# kalibracija.net
KiCad netlist of a schematic drawn in Altium Designer
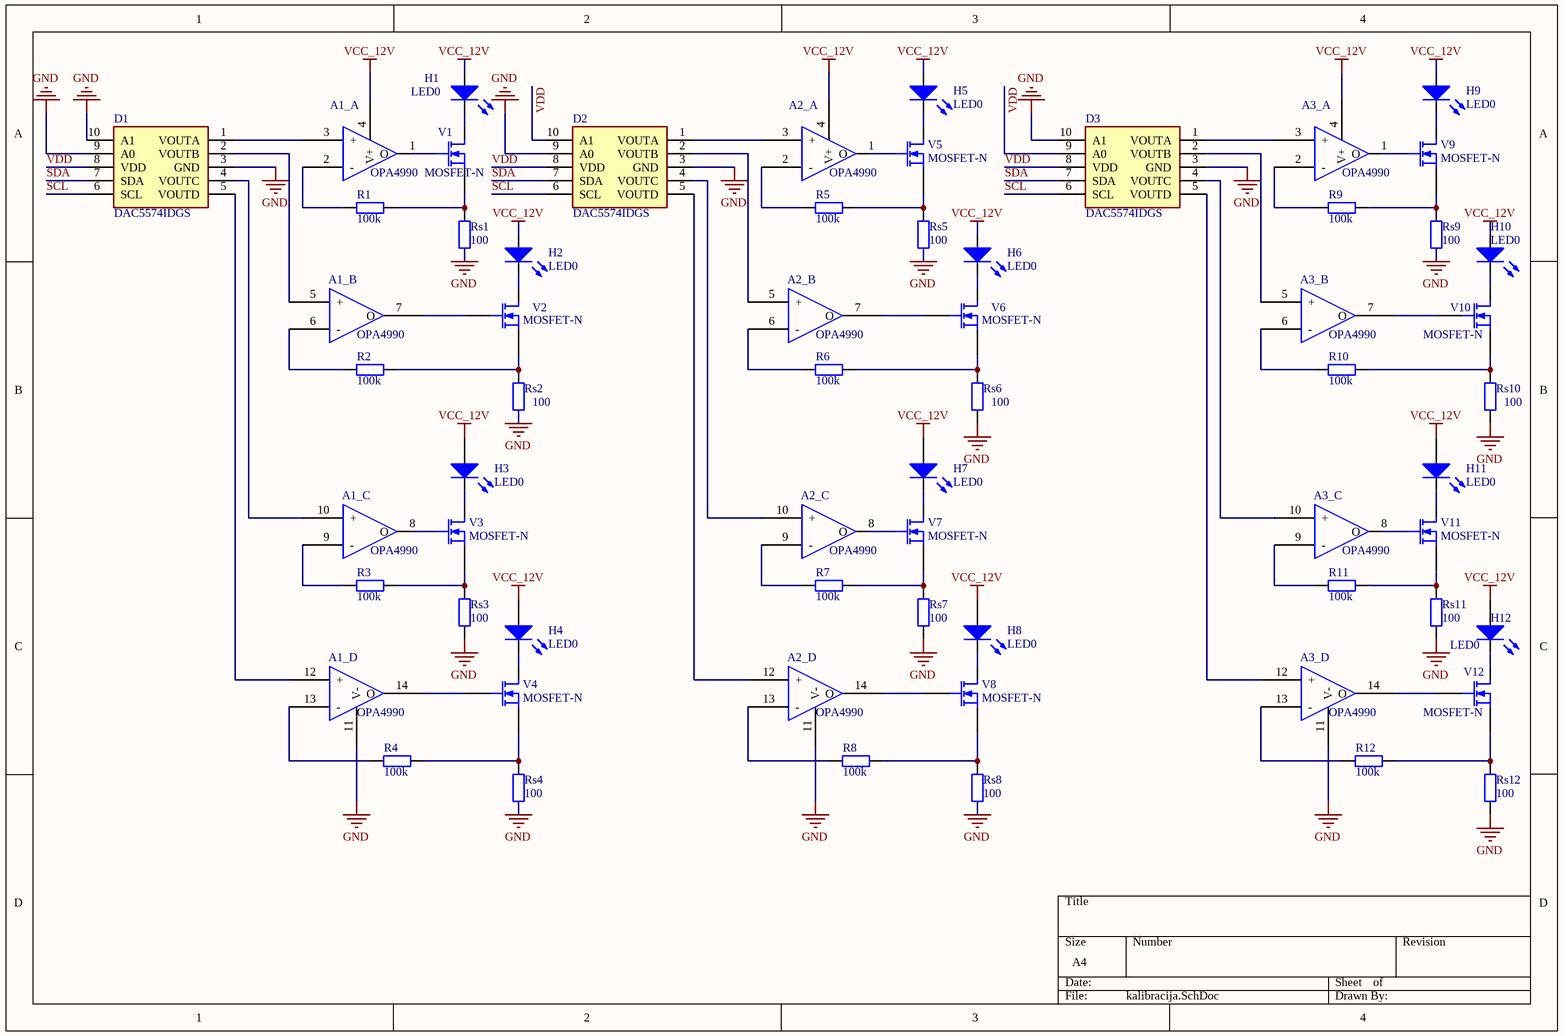
[diagram p0: kalibracija.SchDoc]

(export (version "E")
  (design (tool "Eeschema 10.0.6"))
  (components
    (comp (ref "A1_")
      (value "OPA4990")
      (footprint "SOIC127P600X175-14N")
      (libsource (lib "Kalibracija") (part "OPA4990"))
    )
    (comp (ref "A2_")
      (value "OPA4990")
      (footprint "SOIC127P600X175-14N")
      (libsource (lib "Kalibracija") (part "OPA4990"))
    )
    (comp (ref "A3_")
      (value "OPA4990")
      (footprint "SOIC127P600X175-14N")
      (libsource (lib "Kalibracija") (part "OPA4990"))
    )
    (comp (ref "D1")
      (value "DAC5574IDGS")
      (footprint "SamacSys:SOP50P490X110-10N")
      (description "Integrated Circuit")
      (fields
        (field (name "MOUSER PART NUMBER") "595-DAC5574IDGS")
        (field (name "RS PART NUMBER") "6621533P")
      )
      (libsource (lib "*") (part "DAC5574IDGS"))
    )
    (comp (ref "D2")
      (value "DAC5574IDGS")
      (footprint "SamacSys:SOP50P490X110-10N")
      (description "Integrated Circuit")
      (fields
        (field (name "MOUSER PART NUMBER") "595-DAC5574IDGS")
        (field (name "RS PART NUMBER") "6621533P")
      )
      (libsource (lib "*") (part "DAC5574IDGS"))
    )
    (comp (ref "D3")
      (value "DAC5574IDGS")
      (footprint "SamacSys:SOP50P490X110-10N")
      (description "Integrated Circuit")
      (fields
        (field (name "MOUSER PART NUMBER") "595-DAC5574IDGS")
        (field (name "RS PART NUMBER") "6621533P")
      )
      (libsource (lib "*") (part "DAC5574IDGS"))
    )
    (comp (ref "H1")
      (value "LED0")
      (footprint "HDR1X2")
      (description "Typical INFRARED GaAs LED")
      (fields (field (name "PUBLISHER") "Altium Limited"))
      (libsource (lib "Miscellaneous Devices") (part "LED0"))
    )
    (comp (ref "H2")
      (value "LED0")
      (footprint "HDR1X2")
      (description "Typical INFRARED GaAs LED")
      (fields (field (name "PUBLISHER") "Altium Limited"))
      (libsource (lib "Miscellaneous Devices") (part "LED0"))
    )
    (comp (ref "H3")
      (value "LED0")
      (footprint "HDR1X2")
      (description "Typical INFRARED GaAs LED")
      (fields (field (name "PUBLISHER") "Altium Limited"))
      (libsource (lib "Miscellaneous Devices") (part "LED0"))
    )
    (comp (ref "H4")
      (value "LED0")
      (footprint "HDR1X2")
      (description "Typical INFRARED GaAs LED")
      (fields (field (name "PUBLISHER") "Altium Limited"))
      (libsource (lib "Miscellaneous Devices") (part "LED0"))
    )
    (comp (ref "H5")
      (value "LED0")
      (footprint "HDR1X2")
      (description "Typical INFRARED GaAs LED")
      (fields (field (name "PUBLISHER") "Altium Limited"))
      (libsource (lib "Miscellaneous Devices") (part "LED0"))
    )
    (comp (ref "H6")
      (value "LED0")
      (footprint "HDR1X2")
      (description "Typical INFRARED GaAs LED")
      (fields (field (name "PUBLISHER") "Altium Limited"))
      (libsource (lib "Miscellaneous Devices") (part "LED0"))
    )
    (comp (ref "H7")
      (value "LED0")
      (footprint "HDR1X2")
      (description "Typical INFRARED GaAs LED")
      (fields (field (name "PUBLISHER") "Altium Limited"))
      (libsource (lib "Miscellaneous Devices") (part "LED0"))
    )
    (comp (ref "H8")
      (value "LED0")
      (footprint "HDR1X2")
      (description "Typical INFRARED GaAs LED")
      (fields (field (name "PUBLISHER") "Altium Limited"))
      (libsource (lib "Miscellaneous Devices") (part "LED0"))
    )
    (comp (ref "H9")
      (value "LED0")
      (footprint "HDR1X2")
      (description "Typical INFRARED GaAs LED")
      (fields (field (name "PUBLISHER") "Altium Limited"))
      (libsource (lib "Miscellaneous Devices") (part "LED0"))
    )
    (comp (ref "H10")
      (value "LED0")
      (footprint "HDR1X2")
      (description "Typical INFRARED GaAs LED")
      (fields (field (name "PUBLISHER") "Altium Limited"))
      (libsource (lib "Miscellaneous Devices") (part "LED0"))
    )
    (comp (ref "H11")
      (value "LED0")
      (footprint "HDR1X2")
      (description "Typical INFRARED GaAs LED")
      (fields (field (name "PUBLISHER") "Altium Limited"))
      (libsource (lib "Miscellaneous Devices") (part "LED0"))
    )
    (comp (ref "H12")
      (value "LED0")
      (footprint "HDR1X2")
      (description "Typical INFRARED GaAs LED")
      (fields (field (name "PUBLISHER") "Altium Limited"))
      (libsource (lib "Miscellaneous Devices") (part "LED0"))
    )
    (comp (ref "R1")
      (value "100k")
      (footprint "AXIAL-0.4")
      (description "Resistor")
      (fields (field (name "PUBLISHER") "Altium Limited"))
      (libsource (lib "") (part "Res2_1"))
    )
    (comp (ref "R2")
      (value "100k")
      (footprint "AXIAL-0.4")
      (description "Resistor")
      (fields (field (name "PUBLISHER") "Altium Limited"))
      (libsource (lib "") (part "Res2_1"))
    )
    (comp (ref "R3")
      (value "100k")
      (footprint "AXIAL-0.4")
      (description "Resistor")
      (fields (field (name "PUBLISHER") "Altium Limited"))
      (libsource (lib "") (part "Res2_1"))
    )
    (comp (ref "R4")
      (value "100k")
      (footprint "AXIAL-0.4")
      (description "Resistor")
      (fields (field (name "PUBLISHER") "Altium Limited"))
      (libsource (lib "") (part "Res2_1"))
    )
    (comp (ref "R5")
      (value "100k")
      (footprint "AXIAL-0.4")
      (description "Resistor")
      (fields (field (name "PUBLISHER") "Altium Limited"))
      (libsource (lib "") (part "Res2_1"))
    )
    (comp (ref "R6")
      (value "100k")
      (footprint "AXIAL-0.4")
      (description "Resistor")
      (fields (field (name "PUBLISHER") "Altium Limited"))
      (libsource (lib "") (part "Res2_1"))
    )
    (comp (ref "R7")
      (value "100k")
      (footprint "AXIAL-0.4")
      (description "Resistor")
      (fields (field (name "PUBLISHER") "Altium Limited"))
      (libsource (lib "") (part "Res2_1"))
    )
    (comp (ref "R8")
      (value "100k")
      (footprint "AXIAL-0.4")
      (description "Resistor")
      (fields (field (name "PUBLISHER") "Altium Limited"))
      (libsource (lib "") (part "Res2_1"))
    )
    (comp (ref "R9")
      (value "100k")
      (footprint "AXIAL-0.4")
      (description "Resistor")
      (fields (field (name "PUBLISHER") "Altium Limited"))
      (libsource (lib "") (part "Res2_1"))
    )
    (comp (ref "R10")
      (value "100k")
      (footprint "AXIAL-0.4")
      (description "Resistor")
      (fields (field (name "PUBLISHER") "Altium Limited"))
      (libsource (lib "") (part "Res2_1"))
    )
    (comp (ref "R11")
      (value "100k")
      (footprint "AXIAL-0.4")
      (description "Resistor")
      (fields (field (name "PUBLISHER") "Altium Limited"))
      (libsource (lib "") (part "Res2_1"))
    )
    (comp (ref "R12")
      (value "100k")
      (footprint "AXIAL-0.4")
      (description "Resistor")
      (fields (field (name "PUBLISHER") "Altium Limited"))
      (libsource (lib "") (part "Res2_1"))
    )
    (comp (ref "Rs1")
      (value "100")
      (footprint "AXIAL-0.4")
      (description "Resistor")
      (fields (field (name "PUBLISHER") "Altium Limited"))
      (libsource (lib "Miscellaneous Devices") (part "Res2"))
    )
    (comp (ref "Rs2")
      (value "100")
      (footprint "AXIAL-0.4")
      (description "Resistor")
      (fields (field (name "PUBLISHER") "Altium Limited"))
      (libsource (lib "Miscellaneous Devices") (part "Res2"))
    )
    (comp (ref "Rs3")
      (value "100")
      (footprint "AXIAL-0.4")
      (description "Resistor")
      (fields (field (name "PUBLISHER") "Altium Limited"))
      (libsource (lib "Miscellaneous Devices") (part "Res2"))
    )
    (comp (ref "Rs4")
      (value "100")
      (footprint "AXIAL-0.4")
      (description "Resistor")
      (fields (field (name "PUBLISHER") "Altium Limited"))
      (libsource (lib "Miscellaneous Devices") (part "Res2"))
    )
    (comp (ref "Rs5")
      (value "100")
      (footprint "AXIAL-0.4")
      (description "Resistor")
      (fields (field (name "PUBLISHER") "Altium Limited"))
      (libsource (lib "Miscellaneous Devices") (part "Res2"))
    )
    (comp (ref "Rs6")
      (value "100")
      (footprint "AXIAL-0.4")
      (description "Resistor")
      (fields (field (name "PUBLISHER") "Altium Limited"))
      (libsource (lib "Miscellaneous Devices") (part "Res2"))
    )
    (comp (ref "Rs7")
      (value "100")
      (footprint "AXIAL-0.4")
      (description "Resistor")
      (fields (field (name "PUBLISHER") "Altium Limited"))
      (libsource (lib "Miscellaneous Devices") (part "Res2"))
    )
    (comp (ref "Rs8")
      (value "100")
      (footprint "AXIAL-0.4")
      (description "Resistor")
      (fields (field (name "PUBLISHER") "Altium Limited"))
      (libsource (lib "Miscellaneous Devices") (part "Res2"))
    )
    (comp (ref "Rs9")
      (value "100")
      (footprint "AXIAL-0.4")
      (description "Resistor")
      (fields (field (name "PUBLISHER") "Altium Limited"))
      (libsource (lib "Miscellaneous Devices") (part "Res2"))
    )
    (comp (ref "Rs10")
      (value "100")
      (footprint "AXIAL-0.4")
      (description "Resistor")
      (fields (field (name "PUBLISHER") "Altium Limited"))
      (libsource (lib "Miscellaneous Devices") (part "Res2"))
    )
    (comp (ref "Rs11")
      (value "100")
      (footprint "AXIAL-0.4")
      (description "Resistor")
      (fields (field (name "PUBLISHER") "Altium Limited"))
      (libsource (lib "Miscellaneous Devices") (part "Res2"))
    )
    (comp (ref "Rs12")
      (value "100")
      (footprint "AXIAL-0.4")
      (description "Resistor")
      (fields (field (name "PUBLISHER") "Altium Limited"))
      (libsource (lib "Miscellaneous Devices") (part "Res2"))
    )
    (comp (ref "V1")
      (value "MOSFET-N")
      (footprint "TO-92")
      (description "N-Channel MOSFET")
      (fields (field (name "PUBLISHER") "Altium Limited"))
      (libsource (lib "Miscellaneous Devices") (part "MOSFET-N"))
    )
    (comp (ref "V2")
      (value "MOSFET-N")
      (footprint "TO-92")
      (description "N-Channel MOSFET")
      (fields (field (name "PUBLISHER") "Altium Limited"))
      (libsource (lib "Miscellaneous Devices") (part "MOSFET-N"))
    )
    (comp (ref "V3")
      (value "MOSFET-N")
      (footprint "TO-92")
      (description "N-Channel MOSFET")
      (fields (field (name "PUBLISHER") "Altium Limited"))
      (libsource (lib "Miscellaneous Devices") (part "MOSFET-N"))
    )
    (comp (ref "V4")
      (value "MOSFET-N")
      (footprint "TO-92")
      (description "N-Channel MOSFET")
      (fields (field (name "PUBLISHER") "Altium Limited"))
      (libsource (lib "Miscellaneous Devices") (part "MOSFET-N"))
    )
    (comp (ref "V5")
      (value "MOSFET-N")
      (footprint "TO-92")
      (description "N-Channel MOSFET")
      (fields (field (name "PUBLISHER") "Altium Limited"))
      (libsource (lib "Miscellaneous Devices") (part "MOSFET-N"))
    )
    (comp (ref "V6")
      (value "MOSFET-N")
      (footprint "TO-92")
      (description "N-Channel MOSFET")
      (fields (field (name "PUBLISHER") "Altium Limited"))
      (libsource (lib "Miscellaneous Devices") (part "MOSFET-N"))
    )
    (comp (ref "V7")
      (value "MOSFET-N")
      (footprint "TO-92")
      (description "N-Channel MOSFET")
      (fields (field (name "PUBLISHER") "Altium Limited"))
      (libsource (lib "Miscellaneous Devices") (part "MOSFET-N"))
    )
    (comp (ref "V8")
      (value "MOSFET-N")
      (footprint "TO-92")
      (description "N-Channel MOSFET")
      (fields (field (name "PUBLISHER") "Altium Limited"))
      (libsource (lib "Miscellaneous Devices") (part "MOSFET-N"))
    )
    (comp (ref "V9")
      (value "MOSFET-N")
      (footprint "TO-92")
      (description "N-Channel MOSFET")
      (fields (field (name "PUBLISHER") "Altium Limited"))
      (libsource (lib "Miscellaneous Devices") (part "MOSFET-N"))
    )
    (comp (ref "V10")
      (value "MOSFET-N")
      (footprint "TO-92")
      (description "N-Channel MOSFET")
      (fields (field (name "PUBLISHER") "Altium Limited"))
      (libsource (lib "Miscellaneous Devices") (part "MOSFET-N"))
    )
    (comp (ref "V11")
      (value "MOSFET-N")
      (footprint "TO-92")
      (description "N-Channel MOSFET")
      (fields (field (name "PUBLISHER") "Altium Limited"))
      (libsource (lib "Miscellaneous Devices") (part "MOSFET-N"))
    )
    (comp (ref "V12")
      (value "MOSFET-N")
      (footprint "TO-92")
      (description "N-Channel MOSFET")
      (fields (field (name "PUBLISHER") "Altium Limited"))
      (libsource (lib "Miscellaneous Devices") (part "MOSFET-N"))
    )
  )
  (nets
    (net (code "1") (name "/SCL") (class "Default")
      (node (ref "D1") (pin "6") (pinfunction "SCL_6") (pintype "passive"))
      (node (ref "D2") (pin "6") (pinfunction "SCL_6") (pintype "passive"))
      (node (ref "D3") (pin "6") (pinfunction "SCL_6") (pintype "passive"))
    )
    (net (code "2") (name "/SDA") (class "Default")
      (node (ref "D1") (pin "7") (pinfunction "SDA_7") (pintype "passive"))
      (node (ref "D2") (pin "7") (pinfunction "SDA_7") (pintype "passive"))
      (node (ref "D3") (pin "7") (pinfunction "SDA_7") (pintype "passive"))
    )
    (net (code "3") (name "/VDD") (class "Default")
      (node (ref "D1") (pin "8") (pinfunction "VDD_8") (pintype "passive"))
      (node (ref "D2") (pin "10") (pinfunction "A1_10") (pintype "passive"))
      (node (ref "D2") (pin "8") (pinfunction "VDD_8") (pintype "passive"))
      (node (ref "D3") (pin "8") (pinfunction "VDD_8") (pintype "passive"))
      (node (ref "D3") (pin "9") (pinfunction "A0_9") (pintype "passive"))
    )
    (net (code "4") (name "GND") (class "Default")
      (node (ref "A1_") (pin "11") (pinfunction "V-_11") (pintype "power_in"))
      (node (ref "A2_") (pin "11") (pinfunction "V-_11") (pintype "power_in"))
      (node (ref "A3_") (pin "11") (pinfunction "V-_11") (pintype "power_in"))
      (node (ref "D1") (pin "10") (pinfunction "A1_10") (pintype "passive"))
      (node (ref "D1") (pin "3") (pinfunction "GND_3") (pintype "passive"))
      (node (ref "D1") (pin "9") (pinfunction "A0_9") (pintype "passive"))
      (node (ref "D2") (pin "3") (pinfunction "GND_3") (pintype "passive"))
      (node (ref "D2") (pin "9") (pinfunction "A0_9") (pintype "passive"))
      (node (ref "D3") (pin "10") (pinfunction "A1_10") (pintype "passive"))
      (node (ref "D3") (pin "3") (pinfunction "GND_3") (pintype "passive"))
      (node (ref "Rs1") (pin "1") (pinfunction "1_1") (pintype "passive"))
      (node (ref "Rs10") (pin "1") (pinfunction "1_1") (pintype "passive"))
      (node (ref "Rs11") (pin "1") (pinfunction "1_1") (pintype "passive"))
      (node (ref "Rs12") (pin "1") (pinfunction "1_1") (pintype "passive"))
      (node (ref "Rs2") (pin "1") (pinfunction "1_1") (pintype "passive"))
      (node (ref "Rs3") (pin "1") (pinfunction "1_1") (pintype "passive"))
      (node (ref "Rs4") (pin "1") (pinfunction "1_1") (pintype "passive"))
      (node (ref "Rs5") (pin "1") (pinfunction "1_1") (pintype "passive"))
      (node (ref "Rs6") (pin "1") (pinfunction "1_1") (pintype "passive"))
      (node (ref "Rs7") (pin "1") (pinfunction "1_1") (pintype "passive"))
      (node (ref "Rs8") (pin "1") (pinfunction "1_1") (pintype "passive"))
      (node (ref "Rs9") (pin "1") (pinfunction "1_1") (pintype "passive"))
    )
    (net (code "5") (name "Net-(A1_A-+)") (class "Default")
      (node (ref "A1_") (pin "3") (pinfunction "+_3") (pintype "passive"))
      (node (ref "D1") (pin "1") (pinfunction "VOUTA_1") (pintype "passive"))
    )
    (net (code "6") (name "Net-(A1_A--)") (class "Default")
      (node (ref "A1_") (pin "2") (pinfunction "-_2") (pintype "passive"))
      (node (ref "R1") (pin "1") (pinfunction "1_1") (pintype "passive"))
    )
    (net (code "7") (name "Net-(A1_A-O)") (class "Default")
      (node (ref "A1_") (pin "1") (pinfunction "O_1") (pintype "passive"))
      (node (ref "V1") (pin "2") (pinfunction "G_2") (pintype "passive"))
    )
    (net (code "8") (name "Net-(A1_B-+)") (class "Default")
      (node (ref "A1_") (pin "5") (pinfunction "+_5") (pintype "passive"))
      (node (ref "D1") (pin "2") (pinfunction "VOUTB_2") (pintype "passive"))
    )
    (net (code "9") (name "Net-(A1_B--)") (class "Default")
      (node (ref "A1_") (pin "6") (pinfunction "-_6") (pintype "passive"))
      (node (ref "R2") (pin "1") (pinfunction "1_1") (pintype "passive"))
    )
    (net (code "10") (name "Net-(A1_B-O)") (class "Default")
      (node (ref "A1_") (pin "7") (pinfunction "O_7") (pintype "passive"))
      (node (ref "V2") (pin "2") (pinfunction "G_2") (pintype "passive"))
    )
    (net (code "11") (name "Net-(A1_C-+)") (class "Default")
      (node (ref "A1_") (pin "10") (pinfunction "+_10") (pintype "passive"))
      (node (ref "D1") (pin "4") (pinfunction "VOUTC_4") (pintype "passive"))
    )
    (net (code "12") (name "Net-(A1_C--)") (class "Default")
      (node (ref "A1_") (pin "9") (pinfunction "-_9") (pintype "passive"))
      (node (ref "R3") (pin "1") (pinfunction "1_1") (pintype "passive"))
    )
    (net (code "13") (name "Net-(A1_C-O)") (class "Default")
      (node (ref "A1_") (pin "8") (pinfunction "O_8") (pintype "passive"))
      (node (ref "V3") (pin "2") (pinfunction "G_2") (pintype "passive"))
    )
    (net (code "14") (name "Net-(A1_D-+)") (class "Default")
      (node (ref "A1_") (pin "12") (pinfunction "+_12") (pintype "passive"))
      (node (ref "D1") (pin "5") (pinfunction "VOUTD_5") (pintype "passive"))
    )
    (net (code "15") (name "Net-(A1_D--)") (class "Default")
      (node (ref "A1_") (pin "13") (pinfunction "-_13") (pintype "passive"))
      (node (ref "R4") (pin "1") (pinfunction "1_1") (pintype "passive"))
    )
    (net (code "16") (name "Net-(A1_D-O)") (class "Default")
      (node (ref "A1_") (pin "14") (pinfunction "O_14") (pintype "passive"))
      (node (ref "V4") (pin "2") (pinfunction "G_2") (pintype "passive"))
    )
    (net (code "17") (name "Net-(A2_A-+)") (class "Default")
      (node (ref "A2_") (pin "3") (pinfunction "+_3") (pintype "passive"))
      (node (ref "D2") (pin "1") (pinfunction "VOUTA_1") (pintype "passive"))
    )
    (net (code "18") (name "Net-(A2_A--)") (class "Default")
      (node (ref "A2_") (pin "2") (pinfunction "-_2") (pintype "passive"))
      (node (ref "R5") (pin "1") (pinfunction "1_1") (pintype "passive"))
    )
    (net (code "19") (name "Net-(A2_A-O)") (class "Default")
      (node (ref "A2_") (pin "1") (pinfunction "O_1") (pintype "passive"))
      (node (ref "V5") (pin "2") (pinfunction "G_2") (pintype "passive"))
    )
    (net (code "20") (name "Net-(A2_B-+)") (class "Default")
      (node (ref "A2_") (pin "5") (pinfunction "+_5") (pintype "passive"))
      (node (ref "D2") (pin "2") (pinfunction "VOUTB_2") (pintype "passive"))
    )
    (net (code "21") (name "Net-(A2_B--)") (class "Default")
      (node (ref "A2_") (pin "6") (pinfunction "-_6") (pintype "passive"))
      (node (ref "R6") (pin "1") (pinfunction "1_1") (pintype "passive"))
    )
    (net (code "22") (name "Net-(A2_B-O)") (class "Default")
      (node (ref "A2_") (pin "7") (pinfunction "O_7") (pintype "passive"))
      (node (ref "V6") (pin "2") (pinfunction "G_2") (pintype "passive"))
    )
    (net (code "23") (name "Net-(A2_C-+)") (class "Default")
      (node (ref "A2_") (pin "10") (pinfunction "+_10") (pintype "passive"))
      (node (ref "D2") (pin "4") (pinfunction "VOUTC_4") (pintype "passive"))
    )
    (net (code "24") (name "Net-(A2_C--)") (class "Default")
      (node (ref "A2_") (pin "9") (pinfunction "-_9") (pintype "passive"))
      (node (ref "R7") (pin "1") (pinfunction "1_1") (pintype "passive"))
    )
    (net (code "25") (name "Net-(A2_C-O)") (class "Default")
      (node (ref "A2_") (pin "8") (pinfunction "O_8") (pintype "passive"))
      (node (ref "V7") (pin "2") (pinfunction "G_2") (pintype "passive"))
    )
    (net (code "26") (name "Net-(A2_D-+)") (class "Default")
      (node (ref "A2_") (pin "12") (pinfunction "+_12") (pintype "passive"))
      (node (ref "D2") (pin "5") (pinfunction "VOUTD_5") (pintype "passive"))
    )
    (net (code "27") (name "Net-(A2_D--)") (class "Default")
      (node (ref "A2_") (pin "13") (pinfunction "-_13") (pintype "passive"))
      (node (ref "R8") (pin "1") (pinfunction "1_1") (pintype "passive"))
    )
    (net (code "28") (name "Net-(A2_D-O)") (class "Default")
      (node (ref "A2_") (pin "14") (pinfunction "O_14") (pintype "passive"))
      (node (ref "V8") (pin "2") (pinfunction "G_2") (pintype "passive"))
    )
    (net (code "29") (name "Net-(A3_A-+)") (class "Default")
      (node (ref "A3_") (pin "3") (pinfunction "+_3") (pintype "passive"))
      (node (ref "D3") (pin "1") (pinfunction "VOUTA_1") (pintype "passive"))
    )
    (net (code "30") (name "Net-(A3_A--)") (class "Default")
      (node (ref "A3_") (pin "2") (pinfunction "-_2") (pintype "passive"))
      (node (ref "R9") (pin "1") (pinfunction "1_1") (pintype "passive"))
    )
    (net (code "31") (name "Net-(A3_A-O)") (class "Default")
      (node (ref "A3_") (pin "1") (pinfunction "O_1") (pintype "passive"))
      (node (ref "V9") (pin "2") (pinfunction "G_2") (pintype "passive"))
    )
    (net (code "32") (name "Net-(A3_B-+)") (class "Default")
      (node (ref "A3_") (pin "5") (pinfunction "+_5") (pintype "passive"))
      (node (ref "D3") (pin "2") (pinfunction "VOUTB_2") (pintype "passive"))
    )
    (net (code "33") (name "Net-(A3_B--)") (class "Default")
      (node (ref "A3_") (pin "6") (pinfunction "-_6") (pintype "passive"))
      (node (ref "R10") (pin "1") (pinfunction "1_1") (pintype "passive"))
    )
    (net (code "34") (name "Net-(A3_B-O)") (class "Default")
      (node (ref "A3_") (pin "7") (pinfunction "O_7") (pintype "passive"))
      (node (ref "V10") (pin "2") (pinfunction "G_2") (pintype "passive"))
    )
    (net (code "35") (name "Net-(A3_C-+)") (class "Default")
      (node (ref "A3_") (pin "10") (pinfunction "+_10") (pintype "passive"))
      (node (ref "D3") (pin "4") (pinfunction "VOUTC_4") (pintype "passive"))
    )
    (net (code "36") (name "Net-(A3_C--)") (class "Default")
      (node (ref "A3_") (pin "9") (pinfunction "-_9") (pintype "passive"))
      (node (ref "R11") (pin "1") (pinfunction "1_1") (pintype "passive"))
    )
    (net (code "37") (name "Net-(A3_C-O)") (class "Default")
      (node (ref "A3_") (pin "8") (pinfunction "O_8") (pintype "passive"))
      (node (ref "V11") (pin "2") (pinfunction "G_2") (pintype "passive"))
    )
    (net (code "38") (name "Net-(A3_D-+)") (class "Default")
      (node (ref "A3_") (pin "12") (pinfunction "+_12") (pintype "passive"))
      (node (ref "D3") (pin "5") (pinfunction "VOUTD_5") (pintype "passive"))
    )
    (net (code "39") (name "Net-(A3_D--)") (class "Default")
      (node (ref "A3_") (pin "13") (pinfunction "-_13") (pintype "passive"))
      (node (ref "R12") (pin "1") (pinfunction "1_1") (pintype "passive"))
    )
    (net (code "40") (name "Net-(A3_D-O)") (class "Default")
      (node (ref "A3_") (pin "14") (pinfunction "O_14") (pintype "passive"))
      (node (ref "V12") (pin "2") (pinfunction "G_2") (pintype "passive"))
    )
    (net (code "41") (name "Net-(H1-K)") (class "Default")
      (node (ref "H1") (pin "2") (pinfunction "K_2") (pintype "passive"))
      (node (ref "V1") (pin "1") (pinfunction "D_1") (pintype "passive"))
    )
    (net (code "42") (name "Net-(H2-K)") (class "Default")
      (node (ref "H2") (pin "2") (pinfunction "K_2") (pintype "passive"))
      (node (ref "V2") (pin "1") (pinfunction "D_1") (pintype "passive"))
    )
    (net (code "43") (name "Net-(H3-K)") (class "Default")
      (node (ref "H3") (pin "2") (pinfunction "K_2") (pintype "passive"))
      (node (ref "V3") (pin "1") (pinfunction "D_1") (pintype "passive"))
    )
    (net (code "44") (name "Net-(H4-K)") (class "Default")
      (node (ref "H4") (pin "2") (pinfunction "K_2") (pintype "passive"))
      (node (ref "V4") (pin "1") (pinfunction "D_1") (pintype "passive"))
    )
    (net (code "45") (name "Net-(H5-K)") (class "Default")
      (node (ref "H5") (pin "2") (pinfunction "K_2") (pintype "passive"))
      (node (ref "V5") (pin "1") (pinfunction "D_1") (pintype "passive"))
    )
    (net (code "46") (name "Net-(H6-K)") (class "Default")
      (node (ref "H6") (pin "2") (pinfunction "K_2") (pintype "passive"))
      (node (ref "V6") (pin "1") (pinfunction "D_1") (pintype "passive"))
    )
    (net (code "47") (name "Net-(H7-K)") (class "Default")
      (node (ref "H7") (pin "2") (pinfunction "K_2") (pintype "passive"))
      (node (ref "V7") (pin "1") (pinfunction "D_1") (pintype "passive"))
    )
    (net (code "48") (name "Net-(H8-K)") (class "Default")
      (node (ref "H8") (pin "2") (pinfunction "K_2") (pintype "passive"))
      (node (ref "V8") (pin "1") (pinfunction "D_1") (pintype "passive"))
    )
    (net (code "49") (name "Net-(H9-K)") (class "Default")
      (node (ref "H9") (pin "2") (pinfunction "K_2") (pintype "passive"))
      (node (ref "V9") (pin "1") (pinfunction "D_1") (pintype "passive"))
    )
    (net (code "50") (name "Net-(H10-K)") (class "Default")
      (node (ref "H10") (pin "2") (pinfunction "K_2") (pintype "passive"))
      (node (ref "V10") (pin "1") (pinfunction "D_1") (pintype "passive"))
    )
    (net (code "51") (name "Net-(H11-K)") (class "Default")
      (node (ref "H11") (pin "2") (pinfunction "K_2") (pintype "passive"))
      (node (ref "V11") (pin "1") (pinfunction "D_1") (pintype "passive"))
    )
    (net (code "52") (name "Net-(H12-K)") (class "Default")
      (node (ref "H12") (pin "2") (pinfunction "K_2") (pintype "passive"))
      (node (ref "V12") (pin "1") (pinfunction "D_1") (pintype "passive"))
    )
    (net (code "53") (name "Net-(V1-S)") (class "Default")
      (node (ref "R1") (pin "2") (pinfunction "2_2") (pintype "passive"))
      (node (ref "Rs1") (pin "2") (pinfunction "2_2") (pintype "passive"))
      (node (ref "V1") (pin "3") (pinfunction "S_3") (pintype "passive"))
    )
    (net (code "54") (name "Net-(V2-S)") (class "Default")
      (node (ref "R2") (pin "2") (pinfunction "2_2") (pintype "passive"))
      (node (ref "Rs2") (pin "2") (pinfunction "2_2") (pintype "passive"))
      (node (ref "V2") (pin "3") (pinfunction "S_3") (pintype "passive"))
    )
    (net (code "55") (name "Net-(V3-S)") (class "Default")
      (node (ref "R3") (pin "2") (pinfunction "2_2") (pintype "passive"))
      (node (ref "Rs3") (pin "2") (pinfunction "2_2") (pintype "passive"))
      (node (ref "V3") (pin "3") (pinfunction "S_3") (pintype "passive"))
    )
    (net (code "56") (name "Net-(V4-S)") (class "Default")
      (node (ref "R4") (pin "2") (pinfunction "2_2") (pintype "passive"))
      (node (ref "Rs4") (pin "2") (pinfunction "2_2") (pintype "passive"))
      (node (ref "V4") (pin "3") (pinfunction "S_3") (pintype "passive"))
    )
    (net (code "57") (name "Net-(V5-S)") (class "Default")
      (node (ref "R5") (pin "2") (pinfunction "2_2") (pintype "passive"))
      (node (ref "Rs5") (pin "2") (pinfunction "2_2") (pintype "passive"))
      (node (ref "V5") (pin "3") (pinfunction "S_3") (pintype "passive"))
    )
    (net (code "58") (name "Net-(V6-S)") (class "Default")
      (node (ref "R6") (pin "2") (pinfunction "2_2") (pintype "passive"))
      (node (ref "Rs6") (pin "2") (pinfunction "2_2") (pintype "passive"))
      (node (ref "V6") (pin "3") (pinfunction "S_3") (pintype "passive"))
    )
    (net (code "59") (name "Net-(V7-S)") (class "Default")
      (node (ref "R7") (pin "2") (pinfunction "2_2") (pintype "passive"))
      (node (ref "Rs7") (pin "2") (pinfunction "2_2") (pintype "passive"))
      (node (ref "V7") (pin "3") (pinfunction "S_3") (pintype "passive"))
    )
    (net (code "60") (name "Net-(V8-S)") (class "Default")
      (node (ref "R8") (pin "2") (pinfunction "2_2") (pintype "passive"))
      (node (ref "Rs8") (pin "2") (pinfunction "2_2") (pintype "passive"))
      (node (ref "V8") (pin "3") (pinfunction "S_3") (pintype "passive"))
    )
    (net (code "61") (name "Net-(V9-S)") (class "Default")
      (node (ref "R9") (pin "2") (pinfunction "2_2") (pintype "passive"))
      (node (ref "Rs9") (pin "2") (pinfunction "2_2") (pintype "passive"))
      (node (ref "V9") (pin "3") (pinfunction "S_3") (pintype "passive"))
    )
    (net (code "62") (name "Net-(V10-S)") (class "Default")
      (node (ref "R10") (pin "2") (pinfunction "2_2") (pintype "passive"))
      (node (ref "Rs10") (pin "2") (pinfunction "2_2") (pintype "passive"))
      (node (ref "V10") (pin "3") (pinfunction "S_3") (pintype "passive"))
    )
    (net (code "63") (name "Net-(V11-S)") (class "Default")
      (node (ref "R11") (pin "2") (pinfunction "2_2") (pintype "passive"))
      (node (ref "Rs11") (pin "2") (pinfunction "2_2") (pintype "passive"))
      (node (ref "V11") (pin "3") (pinfunction "S_3") (pintype "passive"))
    )
    (net (code "64") (name "Net-(V12-S)") (class "Default")
      (node (ref "R12") (pin "2") (pinfunction "2_2") (pintype "passive"))
      (node (ref "Rs12") (pin "2") (pinfunction "2_2") (pintype "passive"))
      (node (ref "V12") (pin "3") (pinfunction "S_3") (pintype "passive"))
    )
    (net (code "65") (name "VCC_12V") (class "Default")
      (node (ref "A1_") (pin "4") (pinfunction "V+_4") (pintype "power_in"))
      (node (ref "A2_") (pin "4") (pinfunction "V+_4") (pintype "power_in"))
      (node (ref "A3_") (pin "4") (pinfunction "V+_4") (pintype "power_in"))
      (node (ref "H1") (pin "1") (pinfunction "A_1") (pintype "passive"))
      (node (ref "H10") (pin "1") (pinfunction "A_1") (pintype "passive"))
      (node (ref "H11") (pin "1") (pinfunction "A_1") (pintype "passive"))
      (node (ref "H12") (pin "1") (pinfunction "A_1") (pintype "passive"))
      (node (ref "H2") (pin "1") (pinfunction "A_1") (pintype "passive"))
      (node (ref "H3") (pin "1") (pinfunction "A_1") (pintype "passive"))
      (node (ref "H4") (pin "1") (pinfunction "A_1") (pintype "passive"))
      (node (ref "H5") (pin "1") (pinfunction "A_1") (pintype "passive"))
      (node (ref "H6") (pin "1") (pinfunction "A_1") (pintype "passive"))
      (node (ref "H7") (pin "1") (pinfunction "A_1") (pintype "passive"))
      (node (ref "H8") (pin "1") (pinfunction "A_1") (pintype "passive"))
      (node (ref "H9") (pin "1") (pinfunction "A_1") (pintype "passive"))
    )
  )
)
